# Efm8Midi.net
KiCad netlist of a schematic drawn in EAGLE
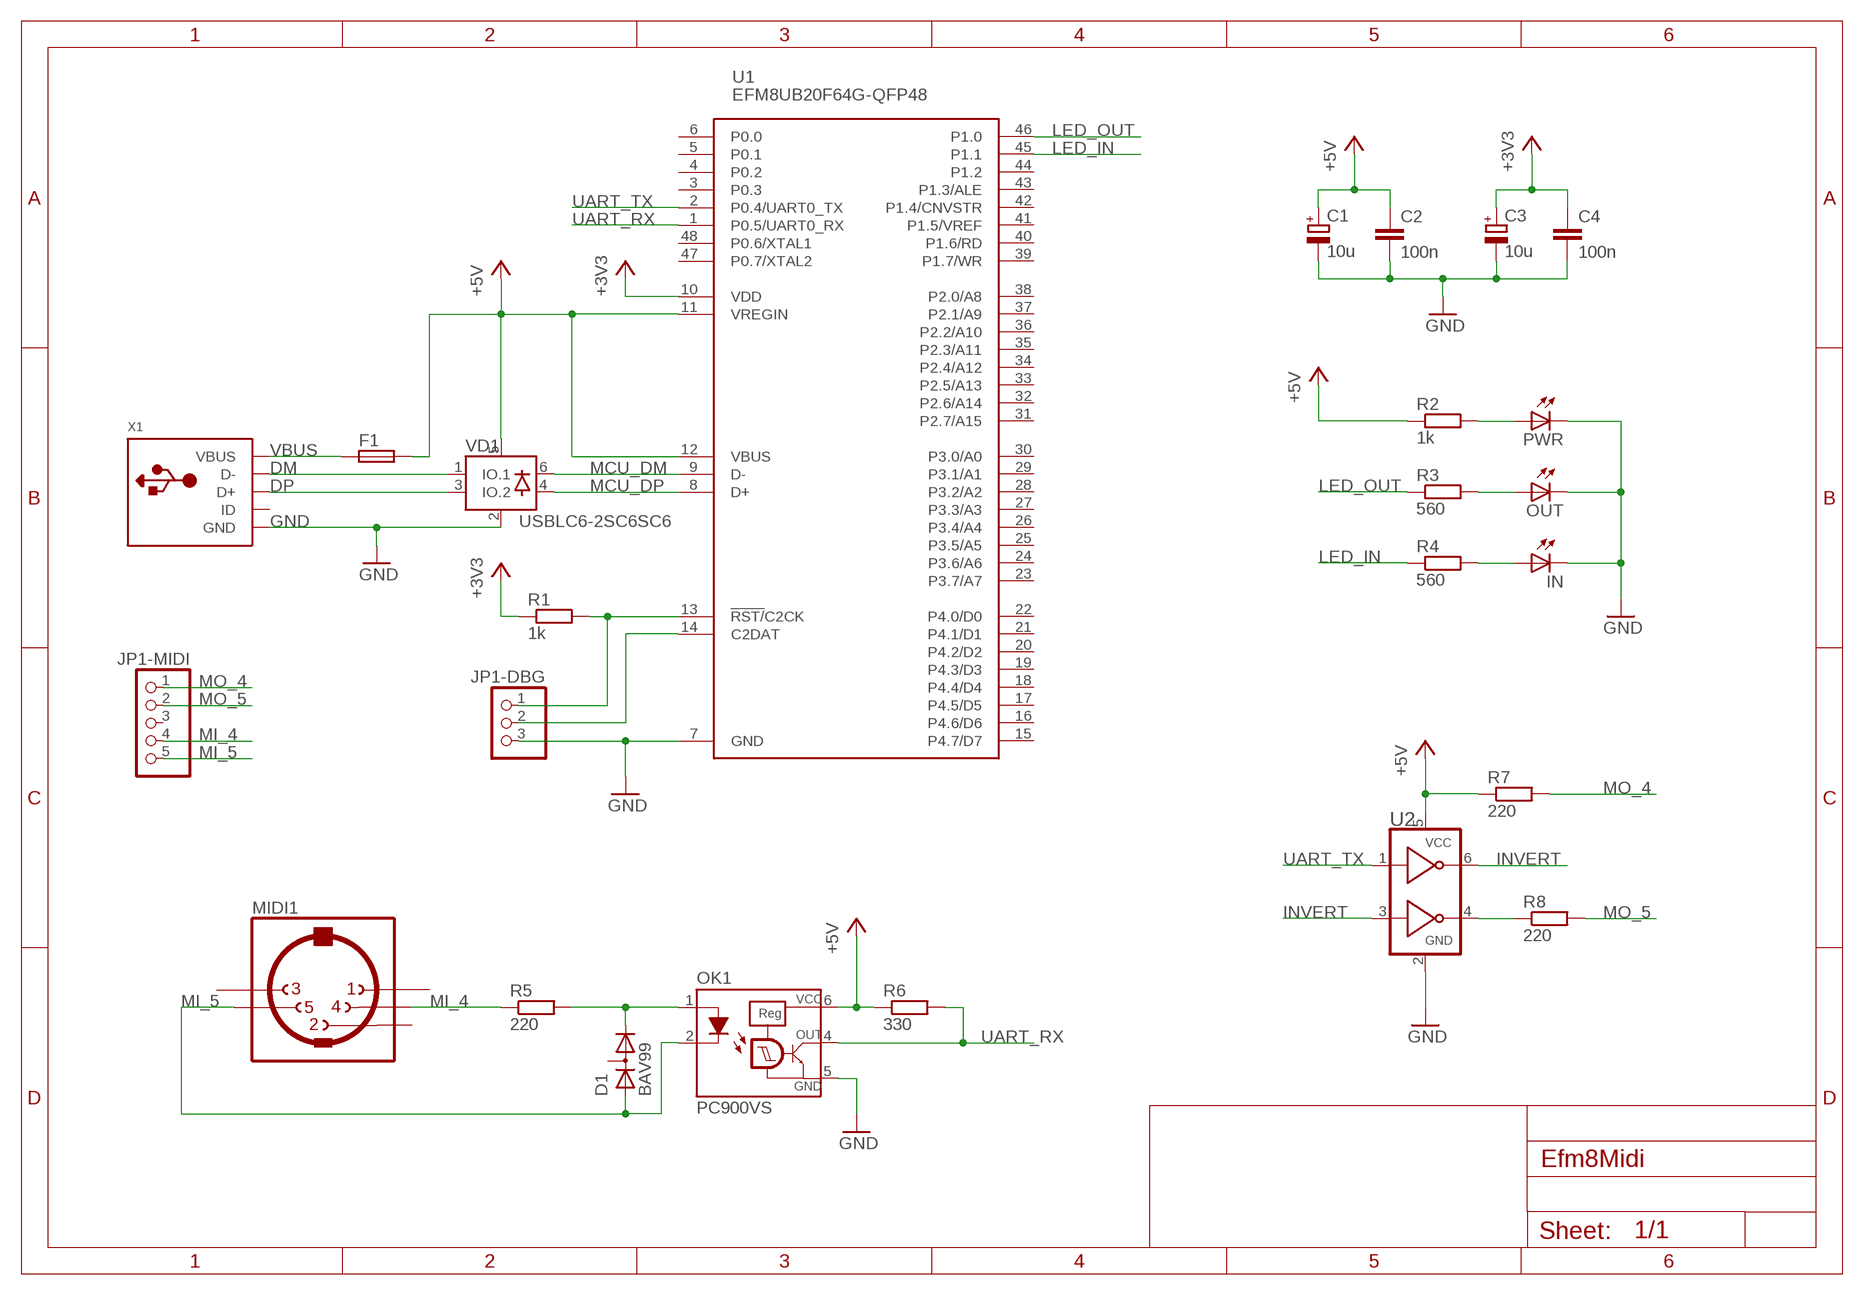
[diagram p0: schematic, sheet 1]

(export (version "E")
  (design (tool "Eeschema 10.0.6"))
  (components
    (comp (ref "C1")
      (value "10u")
      (footprint "eagle-import:CT3216")
      (libsource (lib "eagle-import") (part "CPOL-EUCT3216"))
    )
    (comp (ref "C2")
      (value "100n")
      (footprint "eagle-import:C1206")
      (libsource (lib "eagle-import") (part "C-EUC1206"))
    )
    (comp (ref "C3")
      (value "10u")
      (footprint "eagle-import:CT3216")
      (libsource (lib "eagle-import") (part "CPOL-EUCT3216"))
    )
    (comp (ref "C4")
      (value "100n")
      (footprint "eagle-import:C1206")
      (libsource (lib "eagle-import") (part "C-EUC1206"))
    )
    (comp (ref "D1")
      (value "BAV99")
      (footprint "eagle-import:SOT23")
      (libsource (lib "eagle-import") (part "BAV99"))
    )
    (comp (ref "F1")
      (value "MF-NSMF")
      (footprint "eagle-import:RCL-1206")
      (libsource (lib "eagle-import") (part "MF-NSMF"))
    )
    (comp (ref "IN")
      (value "LED3MM")
      (footprint "eagle-import:LED3MM")
      (libsource (lib "eagle-import") (part "LED3MM"))
    )
    (comp (ref "JP1-DBG")
      (value "PINHD-1X3")
      (footprint "eagle-import:1X03")
      (libsource (lib "eagle-import") (part "PINHD-1X3"))
    )
    (comp (ref "JP1-MIDI")
      (value "PINHD-1X5")
      (footprint "eagle-import:1X05")
      (libsource (lib "eagle-import") (part "PINHD-1X5"))
    )
    (comp (ref "MIDI1")
      (value "MIDIJACK")
      (footprint "eagle-import:MIDI-CP-2350")
      (libsource (lib "eagle-import") (part "MIDIJACK"))
    )
    (comp (ref "OK1")
      (value "PC900VS")
      (footprint "eagle-import:DIL6-SMD")
      (libsource (lib "eagle-import") (part "PC900VS"))
    )
    (comp (ref "OUT")
      (value "LED3MM")
      (footprint "eagle-import:LED3MM")
      (libsource (lib "eagle-import") (part "LED3MM"))
    )
    (comp (ref "PWR")
      (value "LED3MM")
      (footprint "eagle-import:LED3MM")
      (libsource (lib "eagle-import") (part "LED3MM"))
    )
    (comp (ref "R1")
      (value "1k")
      (footprint "eagle-import:R0805")
      (libsource (lib "eagle-import") (part "R-EU_R0805"))
    )
    (comp (ref "R2")
      (value "1k")
      (footprint "eagle-import:R0805")
      (libsource (lib "eagle-import") (part "R-EU_R0805"))
    )
    (comp (ref "R3")
      (value "560")
      (footprint "eagle-import:R0805")
      (libsource (lib "eagle-import") (part "R-EU_R0805"))
    )
    (comp (ref "R4")
      (value "560")
      (footprint "eagle-import:R0805")
      (libsource (lib "eagle-import") (part "R-EU_R0805"))
    )
    (comp (ref "R5")
      (value "220")
      (footprint "eagle-import:R0805")
      (libsource (lib "eagle-import") (part "R-EU_R0805"))
    )
    (comp (ref "R6")
      (value "330")
      (footprint "eagle-import:R0805")
      (libsource (lib "eagle-import") (part "R-EU_R0805"))
    )
    (comp (ref "R7")
      (value "220")
      (footprint "eagle-import:R0805")
      (libsource (lib "eagle-import") (part "R-EU_R0805"))
    )
    (comp (ref "R8")
      (value "220")
      (footprint "eagle-import:R0805")
      (libsource (lib "eagle-import") (part "R-EU_R0805"))
    )
    (comp (ref "U1")
      (value "EFM8UB20F64G-QFP48")
      (footprint "eagle-import:QFP48-7X7-0P5MM")
      (fields (field (name "MFG") "Silicon Laboratories"))
      (libsource (lib "eagle-import") (part "EFM8UB20F64G-QFP48"))
    )
    (comp (ref "U2")
      (value "74LVC2G04SOT-23-6-DBV")
      (footprint "eagle-import:SOT-23-290X160-DBV")
      (libsource (lib "eagle-import") (part "74LVC2G04SOT-23-6-DBV"))
    )
    (comp (ref "VD1")
      (value "USBLC6-2SC6SC6")
      (footprint "eagle-import:SOT-23-6L")
      (libsource (lib "eagle-import") (part "USBLC6-2SC6SC6"))
    )
    (comp (ref "X1")
      (value "MINI-USB-B32005-301")
      (footprint "eagle-import:USB-MINI-B")
      (libsource (lib "eagle-import") (part "MINI-USB-B32005-301"))
    )
  )
  (nets
    (net (code "1") (name "+3V3") (class "Default")
      (node (ref "C3") (pin "+") (pinfunction "+_+") (pintype "passive"))
      (node (ref "C4") (pin "1") (pinfunction "1_1") (pintype "passive"))
      (node (ref "R1") (pin "1") (pinfunction "1_1") (pintype "passive"))
      (node (ref "U1") (pin "10") (pinfunction "VDD_10") (pintype "bidirectional"))
    )
    (net (code "2") (name "+5V") (class "Default")
      (node (ref "C1") (pin "+") (pinfunction "+_+") (pintype "passive"))
      (node (ref "C2") (pin "1") (pinfunction "1_1") (pintype "passive"))
      (node (ref "F1") (pin "2") (pinfunction "2_2") (pintype "passive"))
      (node (ref "OK1") (pin "6") (pinfunction "VCC_6") (pintype "power_in"))
      (node (ref "R2") (pin "1") (pinfunction "1_1") (pintype "passive"))
      (node (ref "R6") (pin "1") (pinfunction "1_1") (pintype "passive"))
      (node (ref "R7") (pin "1") (pinfunction "1_1") (pintype "passive"))
      (node (ref "U1") (pin "11") (pinfunction "VREGIN_11") (pintype "bidirectional"))
      (node (ref "U1") (pin "12") (pinfunction "VBUS_12") (pintype "bidirectional"))
      (node (ref "U2") (pin "5") (pinfunction "VCC_5") (pintype "power_in"))
      (node (ref "VD1") (pin "5") (pinfunction "VBUS_5") (pintype "bidirectional"))
    )
    (net (code "3") (name "/DM") (class "Default")
      (node (ref "VD1") (pin "1") (pinfunction "IO.1_1") (pintype "bidirectional"))
      (node (ref "X1") (pin "D-") (pinfunction "D-_D-") (pintype "bidirectional"))
    )
    (net (code "4") (name "/DP") (class "Default")
      (node (ref "VD1") (pin "3") (pinfunction "IO.2_3") (pintype "bidirectional"))
      (node (ref "X1") (pin "D+") (pinfunction "D+_D+") (pintype "bidirectional"))
    )
    (net (code "5") (name "/INVERT") (class "Default")
      (node (ref "U2") (pin "3") (pinfunction "A2_3") (pintype "input"))
      (node (ref "U2") (pin "6") (pinfunction "Y1_6") (pintype "output"))
    )
    (net (code "6") (name "/LED_IN") (class "Default")
      (node (ref "R4") (pin "1") (pinfunction "1_1") (pintype "passive"))
      (node (ref "U1") (pin "45") (pinfunction "P1.1_45") (pintype "bidirectional"))
    )
    (net (code "7") (name "/LED_OUT") (class "Default")
      (node (ref "R3") (pin "1") (pinfunction "1_1") (pintype "passive"))
      (node (ref "U1") (pin "46") (pinfunction "P1.0_46") (pintype "bidirectional"))
    )
    (net (code "8") (name "/MCU_DM") (class "Default")
      (node (ref "U1") (pin "9") (pinfunction "D-_9") (pintype "bidirectional"))
      (node (ref "VD1") (pin "6") (pinfunction "IO_1_6") (pintype "bidirectional"))
    )
    (net (code "9") (name "/MCU_DP") (class "Default")
      (node (ref "U1") (pin "8") (pinfunction "D+_8") (pintype "bidirectional"))
      (node (ref "VD1") (pin "4") (pinfunction "IO_2_4") (pintype "bidirectional"))
    )
    (net (code "10") (name "/MI_4") (class "Default")
      (node (ref "JP1-MIDI") (pin "4") (pinfunction "4_4") (pintype "passive"))
      (node (ref "MIDI1") (pin "4") (pinfunction "4_4") (pintype "passive"))
      (node (ref "R5") (pin "1") (pinfunction "1_1") (pintype "passive"))
    )
    (net (code "11") (name "/MI_5") (class "Default")
      (node (ref "D1") (pin "1") (pinfunction "A_1") (pintype "passive"))
      (node (ref "JP1-MIDI") (pin "5") (pinfunction "5_5") (pintype "passive"))
      (node (ref "MIDI1") (pin "5") (pinfunction "5_5") (pintype "passive"))
      (node (ref "OK1") (pin "2") (pinfunction "C_2") (pintype "passive"))
    )
    (net (code "12") (name "/MO_4") (class "Default")
      (node (ref "JP1-MIDI") (pin "1") (pinfunction "1_1") (pintype "passive"))
      (node (ref "R7") (pin "2") (pinfunction "2_2") (pintype "passive"))
    )
    (net (code "13") (name "/MO_5") (class "Default")
      (node (ref "JP1-MIDI") (pin "2") (pinfunction "2_2") (pintype "passive"))
      (node (ref "R8") (pin "2") (pinfunction "2_2") (pintype "passive"))
    )
    (net (code "14") (name "/UART_RX") (class "Default")
      (node (ref "OK1") (pin "4") (pinfunction "OUT_4") (pintype "output"))
      (node (ref "R6") (pin "2") (pinfunction "2_2") (pintype "passive"))
      (node (ref "U1") (pin "1") (pinfunction "P0.5/UART0_RX_1") (pintype "bidirectional"))
    )
    (net (code "15") (name "/UART_TX") (class "Default")
      (node (ref "U1") (pin "2") (pinfunction "P0.4/UART0_TX_2") (pintype "bidirectional"))
      (node (ref "U2") (pin "1") (pinfunction "A1_1") (pintype "input"))
    )
    (net (code "16") (name "/VBUS") (class "Default")
      (node (ref "F1") (pin "1") (pinfunction "1_1") (pintype "passive"))
      (node (ref "X1") (pin "VBUS") (pinfunction "VBUS_VBUS") (pintype "power_in"))
    )
    (net (code "17") (name "GND") (class "Default")
      (node (ref "C1") (pin "-") (pinfunction "-_-") (pintype "passive"))
      (node (ref "C2") (pin "2") (pinfunction "2_2") (pintype "passive"))
      (node (ref "C3") (pin "-") (pinfunction "-_-") (pintype "passive"))
      (node (ref "C4") (pin "2") (pinfunction "2_2") (pintype "passive"))
      (node (ref "IN") (pin "K") (pinfunction "C_K") (pintype "passive"))
      (node (ref "JP1-DBG") (pin "3") (pinfunction "3_3") (pintype "passive"))
      (node (ref "OK1") (pin "5") (pinfunction "GND_5") (pintype "power_in"))
      (node (ref "OUT") (pin "K") (pinfunction "C_K") (pintype "passive"))
      (node (ref "PWR") (pin "K") (pinfunction "C_K") (pintype "passive"))
      (node (ref "U1") (pin "7") (pinfunction "GND_7") (pintype "bidirectional"))
      (node (ref "U2") (pin "2") (pinfunction "GND_2") (pintype "passive"))
      (node (ref "VD1") (pin "2") (pinfunction "GND_2") (pintype "bidirectional"))
      (node (ref "X1") (pin "GND") (pinfunction "GND_GND") (pintype "power_in"))
    )
    (net (code "18") (name "Net-(D1-C)") (class "Default")
      (node (ref "D1") (pin "2") (pinfunction "C_2") (pintype "passive"))
      (node (ref "OK1") (pin "1") (pinfunction "A_1") (pintype "passive"))
      (node (ref "R5") (pin "2") (pinfunction "2_2") (pintype "passive"))
    )
    (net (code "19") (name "Net-(IN-PadA)") (class "Default")
      (node (ref "IN") (pin "A") (pinfunction "A_A") (pintype "passive"))
      (node (ref "R4") (pin "2") (pinfunction "2_2") (pintype "passive"))
    )
    (net (code "20") (name "Net-(OUT-PadA)") (class "Default")
      (node (ref "OUT") (pin "A") (pinfunction "A_A") (pintype "passive"))
      (node (ref "R3") (pin "2") (pinfunction "2_2") (pintype "passive"))
    )
    (net (code "21") (name "Net-(PWR-PadA)") (class "Default")
      (node (ref "PWR") (pin "A") (pinfunction "A_A") (pintype "passive"))
      (node (ref "R2") (pin "2") (pinfunction "2_2") (pintype "passive"))
    )
    (net (code "22") (name "Net-(U1-C2DAT)") (class "Default")
      (node (ref "JP1-DBG") (pin "2") (pinfunction "2_2") (pintype "passive"))
      (node (ref "U1") (pin "14") (pinfunction "C2DAT_14") (pintype "bidirectional"))
    )
    (net (code "23") (name "Net-(U1-~{RST{slash}}C2CK)") (class "Default")
      (node (ref "JP1-DBG") (pin "1") (pinfunction "1_1") (pintype "passive"))
      (node (ref "R1") (pin "2") (pinfunction "2_2") (pintype "passive"))
      (node (ref "U1") (pin "13") (pinfunction "~{RST/}C2CK_13") (pintype "bidirectional"))
    )
    (net (code "24") (name "Net-(U2-Y2)") (class "Default")
      (node (ref "R8") (pin "1") (pinfunction "1_1") (pintype "passive"))
      (node (ref "U2") (pin "4") (pinfunction "Y2_4") (pintype "output"))
    )
    (net (code "25") (name "unconnected-(D1-AC-Pad3)") (class "Default")
      (node (ref "D1") (pin "3") (pinfunction "AC_3") (pintype "passive"))
    )
    (net (code "26") (name "unconnected-(JP1-MIDI-Pad3)") (class "Default")
      (node (ref "JP1-MIDI") (pin "3") (pinfunction "3_3") (pintype "passive"))
    )
    (net (code "27") (name "unconnected-(MIDI1-Pad1)") (class "Default")
      (node (ref "MIDI1") (pin "1") (pinfunction "1_1") (pintype "passive"))
    )
    (net (code "28") (name "unconnected-(MIDI1-Pad2)") (class "Default")
      (node (ref "MIDI1") (pin "2") (pinfunction "2_2") (pintype "passive"))
    )
    (net (code "29") (name "unconnected-(MIDI1-Pad3)") (class "Default")
      (node (ref "MIDI1") (pin "3") (pinfunction "3_3") (pintype "passive"))
    )
    (net (code "30") (name "unconnected-(U1-P0.0-Pad6)") (class "Default")
      (node (ref "U1") (pin "6") (pinfunction "P0.0_6") (pintype "bidirectional"))
    )
    (net (code "31") (name "unconnected-(U1-P0.1-Pad5)") (class "Default")
      (node (ref "U1") (pin "5") (pinfunction "P0.1_5") (pintype "bidirectional"))
    )
    (net (code "32") (name "unconnected-(U1-P0.2-Pad4)") (class "Default")
      (node (ref "U1") (pin "4") (pinfunction "P0.2_4") (pintype "bidirectional"))
    )
    (net (code "33") (name "unconnected-(U1-P0.3-Pad3)") (class "Default")
      (node (ref "U1") (pin "3") (pinfunction "P0.3_3") (pintype "bidirectional"))
    )
    (net (code "34") (name "unconnected-(U1-P0.6{slash}XTAL1-Pad48)") (class "Default")
      (node (ref "U1") (pin "48") (pinfunction "P0.6/XTAL1_48") (pintype "bidirectional"))
    )
    (net (code "35") (name "unconnected-(U1-P0.7{slash}XTAL2-Pad47)") (class "Default")
      (node (ref "U1") (pin "47") (pinfunction "P0.7/XTAL2_47") (pintype "bidirectional"))
    )
    (net (code "36") (name "unconnected-(U1-P1.2-Pad44)") (class "Default")
      (node (ref "U1") (pin "44") (pinfunction "P1.2_44") (pintype "bidirectional"))
    )
    (net (code "37") (name "unconnected-(U1-P1.3{slash}ALE-Pad43)") (class "Default")
      (node (ref "U1") (pin "43") (pinfunction "P1.3/ALE_43") (pintype "bidirectional"))
    )
    (net (code "38") (name "unconnected-(U1-P1.4{slash}CNVSTR-Pad42)") (class "Default")
      (node (ref "U1") (pin "42") (pinfunction "P1.4/CNVSTR_42") (pintype "bidirectional"))
    )
    (net (code "39") (name "unconnected-(U1-P1.5{slash}VREF-Pad41)") (class "Default")
      (node (ref "U1") (pin "41") (pinfunction "P1.5/VREF_41") (pintype "bidirectional"))
    )
    (net (code "40") (name "unconnected-(U1-P1.6{slash}RD-Pad40)") (class "Default")
      (node (ref "U1") (pin "40") (pinfunction "P1.6/RD_40") (pintype "bidirectional"))
    )
    (net (code "41") (name "unconnected-(U1-P1.7{slash}WR-Pad39)") (class "Default")
      (node (ref "U1") (pin "39") (pinfunction "P1.7/WR_39") (pintype "bidirectional"))
    )
    (net (code "42") (name "unconnected-(U1-P2.0{slash}A8-Pad38)") (class "Default")
      (node (ref "U1") (pin "38") (pinfunction "P2.0/A8_38") (pintype "bidirectional"))
    )
    (net (code "43") (name "unconnected-(U1-P2.1{slash}A9-Pad37)") (class "Default")
      (node (ref "U1") (pin "37") (pinfunction "P2.1/A9_37") (pintype "bidirectional"))
    )
    (net (code "44") (name "unconnected-(U1-P2.2{slash}A10-Pad36)") (class "Default")
      (node (ref "U1") (pin "36") (pinfunction "P2.2/A10_36") (pintype "bidirectional"))
    )
    (net (code "45") (name "unconnected-(U1-P2.3{slash}A11-Pad35)") (class "Default")
      (node (ref "U1") (pin "35") (pinfunction "P2.3/A11_35") (pintype "bidirectional"))
    )
    (net (code "46") (name "unconnected-(U1-P2.4{slash}A12-Pad34)") (class "Default")
      (node (ref "U1") (pin "34") (pinfunction "P2.4/A12_34") (pintype "bidirectional"))
    )
    (net (code "47") (name "unconnected-(U1-P2.5{slash}A13-Pad33)") (class "Default")
      (node (ref "U1") (pin "33") (pinfunction "P2.5/A13_33") (pintype "bidirectional"))
    )
    (net (code "48") (name "unconnected-(U1-P2.6{slash}A14-Pad32)") (class "Default")
      (node (ref "U1") (pin "32") (pinfunction "P2.6/A14_32") (pintype "bidirectional"))
    )
    (net (code "49") (name "unconnected-(U1-P2.7{slash}A15-Pad31)") (class "Default")
      (node (ref "U1") (pin "31") (pinfunction "P2.7/A15_31") (pintype "bidirectional"))
    )
    (net (code "50") (name "unconnected-(U1-P3.0{slash}A0-Pad30)") (class "Default")
      (node (ref "U1") (pin "30") (pinfunction "P3.0/A0_30") (pintype "bidirectional"))
    )
    (net (code "51") (name "unconnected-(U1-P3.1{slash}A1-Pad29)") (class "Default")
      (node (ref "U1") (pin "29") (pinfunction "P3.1/A1_29") (pintype "bidirectional"))
    )
    (net (code "52") (name "unconnected-(U1-P3.2{slash}A2-Pad28)") (class "Default")
      (node (ref "U1") (pin "28") (pinfunction "P3.2/A2_28") (pintype "bidirectional"))
    )
    (net (code "53") (name "unconnected-(U1-P3.3{slash}A3-Pad27)") (class "Default")
      (node (ref "U1") (pin "27") (pinfunction "P3.3/A3_27") (pintype "bidirectional"))
    )
    (net (code "54") (name "unconnected-(U1-P3.4{slash}A4-Pad26)") (class "Default")
      (node (ref "U1") (pin "26") (pinfunction "P3.4/A4_26") (pintype "bidirectional"))
    )
    (net (code "55") (name "unconnected-(U1-P3.5{slash}A5-Pad25)") (class "Default")
      (node (ref "U1") (pin "25") (pinfunction "P3.5/A5_25") (pintype "bidirectional"))
    )
    (net (code "56") (name "unconnected-(U1-P3.6{slash}A6-Pad24)") (class "Default")
      (node (ref "U1") (pin "24") (pinfunction "P3.6/A6_24") (pintype "bidirectional"))
    )
    (net (code "57") (name "unconnected-(U1-P3.7{slash}A7-Pad23)") (class "Default")
      (node (ref "U1") (pin "23") (pinfunction "P3.7/A7_23") (pintype "bidirectional"))
    )
    (net (code "58") (name "unconnected-(U1-P4.0{slash}D0-Pad22)") (class "Default")
      (node (ref "U1") (pin "22") (pinfunction "P4.0/D0_22") (pintype "bidirectional"))
    )
    (net (code "59") (name "unconnected-(U1-P4.1{slash}D1-Pad21)") (class "Default")
      (node (ref "U1") (pin "21") (pinfunction "P4.1/D1_21") (pintype "bidirectional"))
    )
    (net (code "60") (name "unconnected-(U1-P4.2{slash}D2-Pad20)") (class "Default")
      (node (ref "U1") (pin "20") (pinfunction "P4.2/D2_20") (pintype "bidirectional"))
    )
    (net (code "61") (name "unconnected-(U1-P4.3{slash}D3-Pad19)") (class "Default")
      (node (ref "U1") (pin "19") (pinfunction "P4.3/D3_19") (pintype "bidirectional"))
    )
    (net (code "62") (name "unconnected-(U1-P4.4{slash}D4-Pad18)") (class "Default")
      (node (ref "U1") (pin "18") (pinfunction "P4.4/D4_18") (pintype "bidirectional"))
    )
    (net (code "63") (name "unconnected-(U1-P4.5{slash}D5-Pad17)") (class "Default")
      (node (ref "U1") (pin "17") (pinfunction "P4.5/D5_17") (pintype "bidirectional"))
    )
    (net (code "64") (name "unconnected-(U1-P4.6{slash}D6-Pad16)") (class "Default")
      (node (ref "U1") (pin "16") (pinfunction "P4.6/D6_16") (pintype "bidirectional"))
    )
    (net (code "65") (name "unconnected-(U1-P4.7{slash}D7-Pad15)") (class "Default")
      (node (ref "U1") (pin "15") (pinfunction "P4.7/D7_15") (pintype "bidirectional"))
    )
    (net (code "66") (name "unconnected-(X1-PadID)") (class "Default")
      (node (ref "X1") (pin "ID") (pinfunction "ID_ID") (pintype "bidirectional"))
    )
  )
)
